# Sheet1.net
KiCad netlist of a schematic drawn in Altium Designer
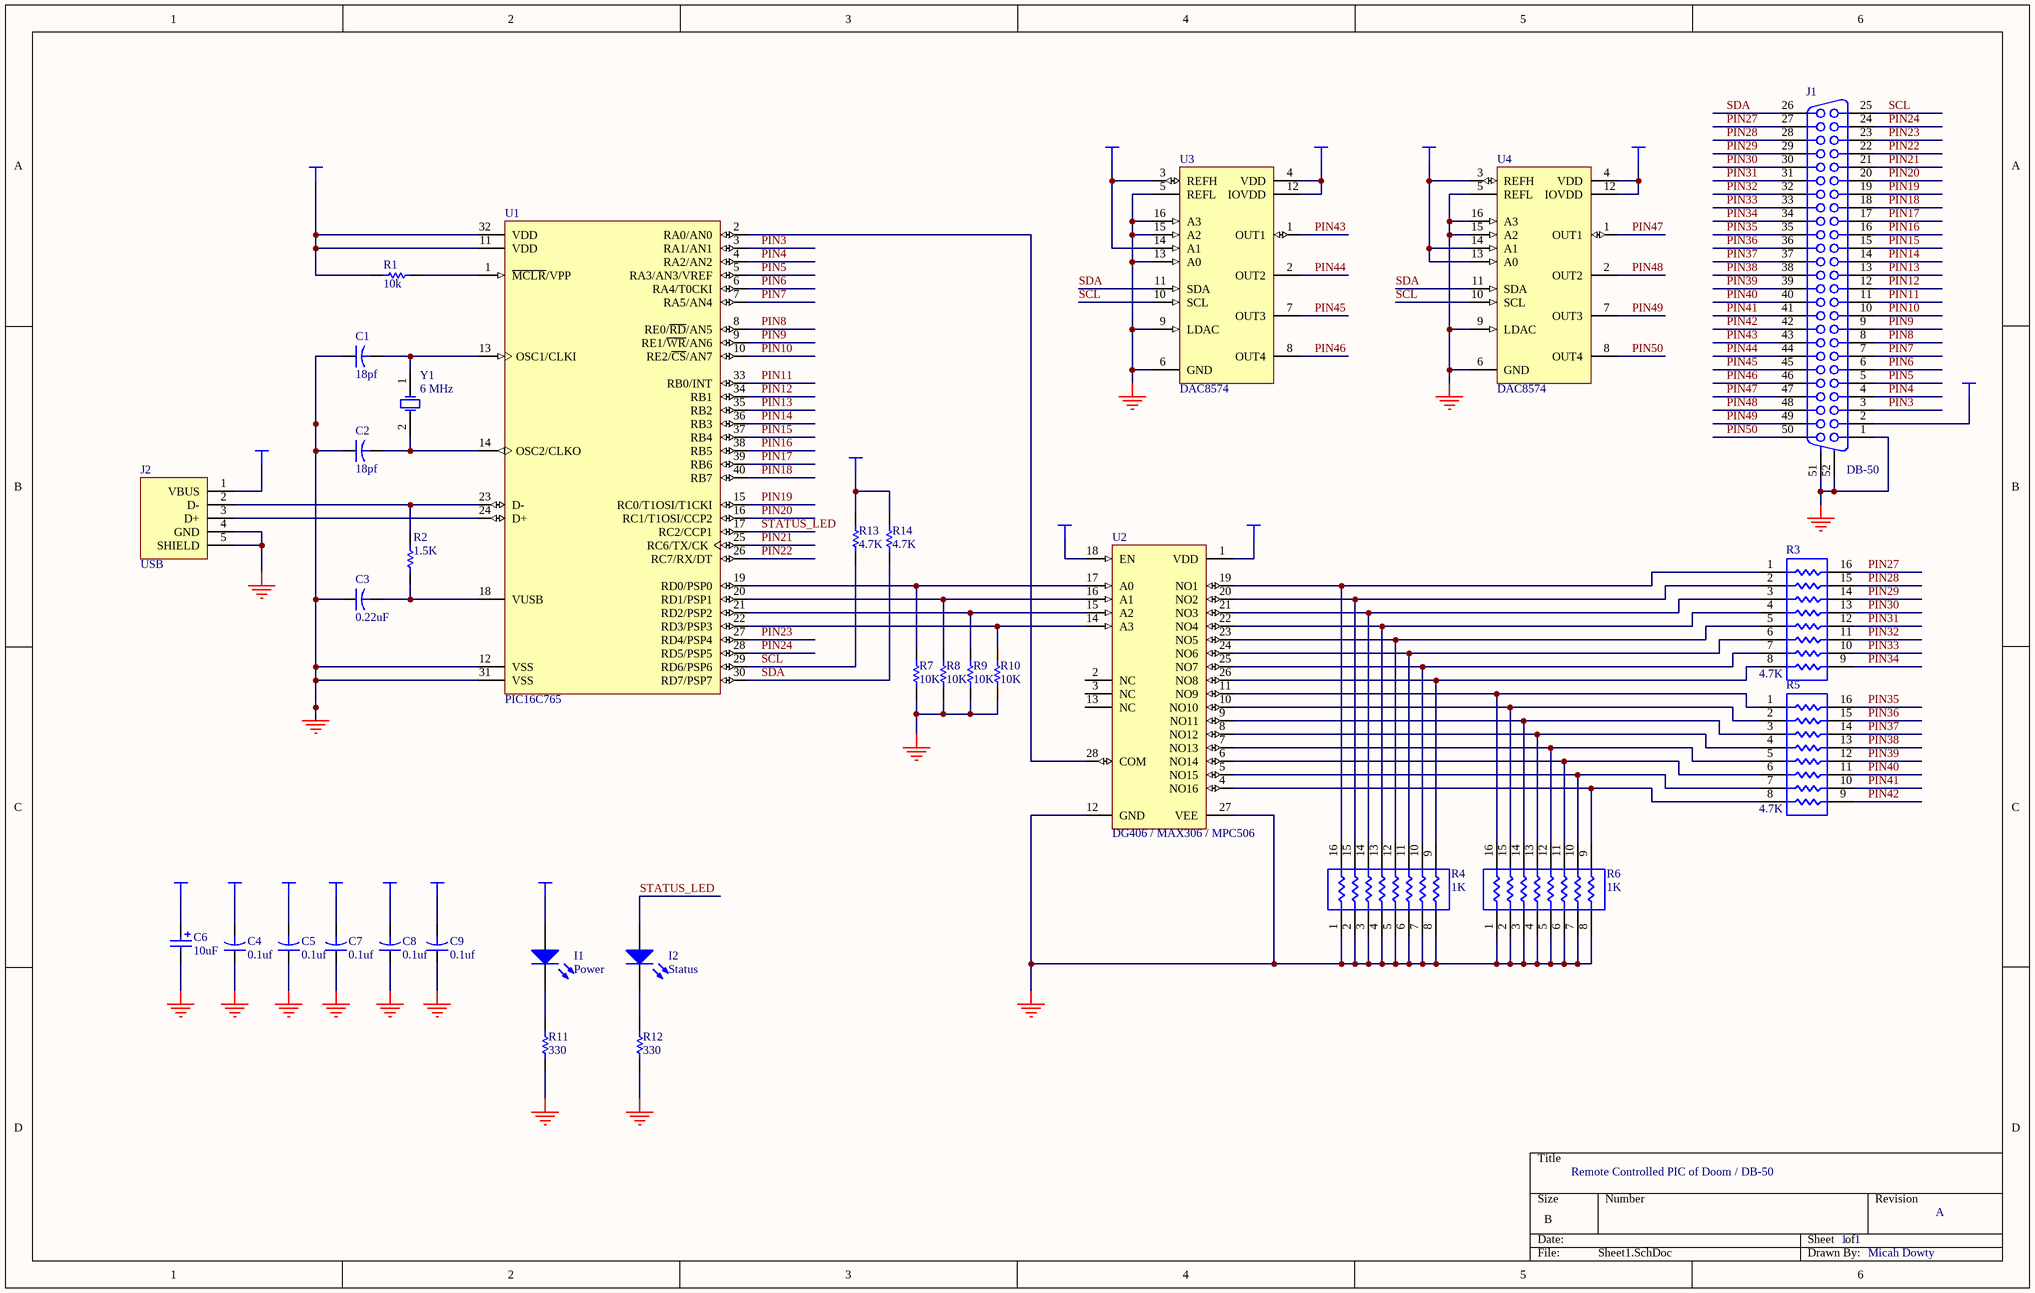
[diagram p0: Sheet1.SchDoc]

(export (version "E")
  (design (tool "Eeschema 10.0.6"))
  (components
    (comp (ref "C1")
      (value "Cap2")
      (footprint "C1005-0402")
      (description "Capacitor")
      (fields
        (field (name "MANUFACTURER") "Generic Components")
        (field (name "ALTIUM_VALUE") "18pf")
        (field (name "PUBLISHER") "Altium Limited")
      )
      (libsource (lib "Miscellaneous Devices") (part "Cap2"))
    )
    (comp (ref "C2")
      (value "Cap2")
      (footprint "C1005-0402")
      (description "Capacitor")
      (fields
        (field (name "MANUFACTURER") "Generic Components")
        (field (name "ALTIUM_VALUE") "18pf")
        (field (name "PUBLISHER") "Altium Limited")
      )
      (libsource (lib "Miscellaneous Devices") (part "Cap2"))
    )
    (comp (ref "C3")
      (value "0.22uF")
      (footprint "C1005-0402")
      (description "Capacitor")
      (fields (field (name "MANUFACTURER") "Generic Components") (field (name "PUBLISHER") "Altium Limited"))
      (libsource (lib "Miscellaneous Devices") (part "Cap2"))
    )
    (comp (ref "C4")
      (value "0.1uf")
      (footprint "C1005-0402")
      (description "Capacitor")
      (fields (field (name "MANUFACTURER") "Generic Components") (field (name "PUBLISHER") "Altium Limited"))
      (libsource (lib "Miscellaneous Devices") (part "Cap2"))
    )
    (comp (ref "C5")
      (value "0.1uf")
      (footprint "C1005-0402")
      (description "Capacitor")
      (fields (field (name "MANUFACTURER") "Generic Components") (field (name "PUBLISHER") "Altium Limited"))
      (libsource (lib "Miscellaneous Devices") (part "Cap2"))
    )
    (comp (ref "C6")
      (value "10uF")
      (footprint "CC4532-1812/Y1.8")
      (description "Polarized Capacitor (Radial)")
      (fields (field (name "MANUFACTURER") "Generic Components") (field (name "PUBLISHER") "Altium Limited"))
      (libsource (lib "Miscellaneous Devices") (part "Cap Pol1"))
    )
    (comp (ref "C7")
      (value "0.1uf")
      (footprint "C1005-0402")
      (description "Capacitor")
      (fields (field (name "MANUFACTURER") "Generic Components") (field (name "PUBLISHER") "Altium Limited"))
      (libsource (lib "Miscellaneous Devices") (part "Cap2"))
    )
    (comp (ref "C8")
      (value "0.1uf")
      (footprint "C1005-0402")
      (description "Capacitor")
      (fields (field (name "MANUFACTURER") "Generic Components") (field (name "PUBLISHER") "Altium Limited"))
      (libsource (lib "Miscellaneous Devices") (part "Cap2"))
    )
    (comp (ref "C9")
      (value "0.1uf")
      (footprint "C1005-0402")
      (description "Capacitor")
      (fields (field (name "MANUFACTURER") "Generic Components") (field (name "PUBLISHER") "Altium Limited"))
      (libsource (lib "Miscellaneous Devices") (part "Cap2"))
    )
    (comp (ref "I1")
      (value "Power")
      (footprint "LED-1-UNBROKE")
      (description "Typical RED GaAs LED")
      (fields (field (name "MANUFACTURER") "Generic Components") (field (name "PUBLISHER") "Altium Limited"))
      (libsource (lib "Miscellaneous Devices") (part "LED1"))
    )
    (comp (ref "I2")
      (value "Status")
      (footprint "LED-1-UNBROKE")
      (description "Typical RED GaAs LED")
      (fields (field (name "MANUFACTURER") "Generic Components") (field (name "PUBLISHER") "Altium Limited"))
      (libsource (lib "Miscellaneous Devices") (part "LED1"))
    )
    (comp (ref "J1")
      (value "DB-50")
      (footprint "NORCOMP-DB50")
      (description "Receptacle Header Assemby")
      (fields (field (name "MANUFACTURER") "Generic Components") (field (name "PUBLISHER") "Altium Limited"))
      (libsource (lib "Miscellaneous Connectors") (part "Connector 50"))
    )
    (comp (ref "J2")
      (value "USB")
      (footprint "USB-TYPEB")
      (description "Header, 4-Pin")
      (fields (field (name "MANUFACTURER") "Generic Components") (field (name "PUBLISHER") "Altium Limited"))
      (libsource (lib "parts") (part "USB Type B"))
    )
    (comp (ref "R1")
      (value "Res1")
      (footprint "C1005-0402")
      (description "Resistor")
      (fields
        (field (name "MANUFACTURER") "Generic Components")
        (field (name "ALTIUM_VALUE") "10k")
        (field (name "PUBLISHER") "Altium Limited")
      )
      (libsource (lib "Miscellaneous Devices") (part "Res1"))
    )
    (comp (ref "R2")
      (value "Res1")
      (footprint "C1005-0402")
      (description "Resistor")
      (fields
        (field (name "MANUFACTURER") "Generic Components")
        (field (name "ALTIUM_VALUE") "1.5K")
        (field (name "PUBLISHER") "Altium Limited")
      )
      (libsource (lib "Miscellaneous Devices") (part "Res1"))
    )
    (comp (ref "R3")
      (value "4.7K")
      (footprint "EXB2HV")
      (description "Resistor Array")
      (fields (field (name "MANUFACTURER") "Generic Components") (field (name "PUBLISHER") "Altium Limited"))
      (libsource (lib "Miscellaneous Devices") (part "Res Pack3"))
    )
    (comp (ref "R4")
      (value "1K")
      (footprint "EXB2HV")
      (description "Resistor Array")
      (fields (field (name "MANUFACTURER") "Generic Components") (field (name "PUBLISHER") "Altium Limited"))
      (libsource (lib "Miscellaneous Devices") (part "Res Pack3"))
    )
    (comp (ref "R5")
      (value "4.7K")
      (footprint "EXB2HV")
      (description "Resistor Array")
      (fields (field (name "MANUFACTURER") "Generic Components") (field (name "PUBLISHER") "Altium Limited"))
      (libsource (lib "Miscellaneous Devices") (part "Res Pack3"))
    )
    (comp (ref "R6")
      (value "1K")
      (footprint "EXB2HV")
      (description "Resistor Array")
      (fields (field (name "MANUFACTURER") "Generic Components") (field (name "PUBLISHER") "Altium Limited"))
      (libsource (lib "Miscellaneous Devices") (part "Res Pack3"))
    )
    (comp (ref "R7")
      (value "10K")
      (footprint "C1005-0402")
      (description "Resistor")
      (fields (field (name "MANUFACTURER") "Generic Components") (field (name "PUBLISHER") "Altium Limited"))
      (libsource (lib "Miscellaneous Devices") (part "Res1"))
    )
    (comp (ref "R8")
      (value "10K")
      (footprint "C1005-0402")
      (description "Resistor")
      (fields (field (name "MANUFACTURER") "Generic Components") (field (name "PUBLISHER") "Altium Limited"))
      (libsource (lib "Miscellaneous Devices") (part "Res1"))
    )
    (comp (ref "R9")
      (value "10K")
      (footprint "C1005-0402")
      (description "Resistor")
      (fields (field (name "MANUFACTURER") "Generic Components") (field (name "PUBLISHER") "Altium Limited"))
      (libsource (lib "Miscellaneous Devices") (part "Res1"))
    )
    (comp (ref "R10")
      (value "10K")
      (footprint "C1005-0402")
      (description "Resistor")
      (fields (field (name "MANUFACTURER") "Generic Components") (field (name "PUBLISHER") "Altium Limited"))
      (libsource (lib "Miscellaneous Devices") (part "Res1"))
    )
    (comp (ref "R11")
      (value "330")
      (footprint "C1005-0402")
      (description "Resistor")
      (fields (field (name "MANUFACTURER") "Generic Components") (field (name "PUBLISHER") "Altium Limited"))
      (libsource (lib "Miscellaneous Devices") (part "Res1"))
    )
    (comp (ref "R12")
      (value "330")
      (footprint "C1005-0402")
      (description "Resistor")
      (fields (field (name "MANUFACTURER") "Generic Components") (field (name "PUBLISHER") "Altium Limited"))
      (libsource (lib "Miscellaneous Devices") (part "Res1"))
    )
    (comp (ref "R13")
      (value "4.7K")
      (footprint "C1005-0402")
      (description "Resistor")
      (fields (field (name "MANUFACTURER") "Generic Components") (field (name "PUBLISHER") "Altium Limited"))
      (libsource (lib "Miscellaneous Devices") (part "Res1"))
    )
    (comp (ref "R14")
      (value "4.7K")
      (footprint "C1005-0402")
      (description "Resistor")
      (fields (field (name "MANUFACTURER") "Generic Components") (field (name "PUBLISHER") "Altium Limited"))
      (libsource (lib "Miscellaneous Devices") (part "Res1"))
    )
    (comp (ref "U1")
      (value "PIC16C765")
      (footprint "DIP-40")
      (description "EPROM-Based 8-Bit CMOS Microcontroller with USB")
      (fields (field (name "MANUFACTURER") "Microchip"))
      (libsource (lib "parts") (part "PIC16C765"))
    )
    (comp (ref "U2")
      (value "DG406 / MAX306 / MPC506")
      (footprint "SO-G28/G7.45")
      (description "Precision, 16-Channel High-performance, CMOS Analog Multiplexer")
      (fields (field (name "MANUFACTURER") "Maxim") (field (name "PUBLISHER") "Altium Limited"))
      (libsource (lib "Maxim Logic Multiplexer") (part "MAX306EPI"))
    )
    (comp (ref "U3")
      (value "DAC8574")
      (footprint "TSSO5X6-G16")
      (description "Quad 16-Bit Low Power Voltage Output I2C Interface DAC")
      (fields (field (name "MANUFACTURER") "Texas Instruments"))
      (libsource (lib "parts") (part "DAC8574"))
    )
    (comp (ref "U4")
      (value "DAC8574")
      (footprint "TSSO5X6-G16")
      (description "Quad 16-Bit Low Power Voltage Output I2C Interface DAC")
      (fields (field (name "MANUFACTURER") "Texas Instruments"))
      (libsource (lib "parts") (part "DAC8574"))
    )
    (comp (ref "Y1")
      (value "6 MHz")
      (footprint "BCY-W2/E4.7")
      (description "Crystal Oscillator")
      (fields (field (name "MANUFACTURER") "Generic Components") (field (name "PUBLISHER") "Altium Limited"))
      (libsource (lib "Miscellaneous Devices") (part "XTAL"))
    )
  )
  (nets
    (net (code "1") (name "/PIN3") (class "Default")
      (node (ref "J1") (pin "3") (pinfunction "3_3") (pintype "passive"))
      (node (ref "U1") (pin "3") (pinfunction "RA1/AN1_3") (pintype "bidirectional"))
    )
    (net (code "2") (name "/PIN4") (class "Default")
      (node (ref "J1") (pin "4") (pinfunction "4_4") (pintype "passive"))
      (node (ref "U1") (pin "4") (pinfunction "RA2/AN2_4") (pintype "bidirectional"))
    )
    (net (code "3") (name "/PIN5") (class "Default")
      (node (ref "J1") (pin "5") (pinfunction "5_5") (pintype "passive"))
      (node (ref "U1") (pin "5") (pinfunction "RA3/AN3/VREF_5") (pintype "bidirectional"))
    )
    (net (code "4") (name "/PIN6") (class "Default")
      (node (ref "J1") (pin "6") (pinfunction "6_6") (pintype "passive"))
      (node (ref "U1") (pin "6") (pinfunction "RA4/T0CKI_6") (pintype "bidirectional"))
    )
    (net (code "5") (name "/PIN7") (class "Default")
      (node (ref "J1") (pin "7") (pinfunction "7_7") (pintype "passive"))
      (node (ref "U1") (pin "7") (pinfunction "RA5/AN4_7") (pintype "bidirectional"))
    )
    (net (code "6") (name "/PIN8") (class "Default")
      (node (ref "J1") (pin "8") (pinfunction "8_8") (pintype "passive"))
      (node (ref "U1") (pin "8") (pinfunction "RE0/~{RD}/AN5_8") (pintype "bidirectional"))
    )
    (net (code "7") (name "/PIN9") (class "Default")
      (node (ref "J1") (pin "9") (pinfunction "9_9") (pintype "passive"))
      (node (ref "U1") (pin "9") (pinfunction "RE1/~{WR}/AN6_9") (pintype "bidirectional"))
    )
    (net (code "8") (name "/PIN10") (class "Default")
      (node (ref "J1") (pin "10") (pinfunction "10_10") (pintype "passive"))
      (node (ref "U1") (pin "10") (pinfunction "RE2/~{CS}/AN7_10") (pintype "bidirectional"))
    )
    (net (code "9") (name "/PIN11") (class "Default")
      (node (ref "J1") (pin "11") (pinfunction "11_11") (pintype "passive"))
      (node (ref "U1") (pin "33") (pinfunction "RB0/INT_33") (pintype "bidirectional"))
    )
    (net (code "10") (name "/PIN12") (class "Default")
      (node (ref "J1") (pin "12") (pinfunction "12_12") (pintype "passive"))
      (node (ref "U1") (pin "34") (pinfunction "RB1_34") (pintype "bidirectional"))
    )
    (net (code "11") (name "/PIN13") (class "Default")
      (node (ref "J1") (pin "13") (pinfunction "13_13") (pintype "passive"))
      (node (ref "U1") (pin "35") (pinfunction "RB2_35") (pintype "bidirectional"))
    )
    (net (code "12") (name "/PIN14") (class "Default")
      (node (ref "J1") (pin "14") (pinfunction "14_14") (pintype "passive"))
      (node (ref "U1") (pin "36") (pinfunction "RB3_36") (pintype "bidirectional"))
    )
    (net (code "13") (name "/PIN15") (class "Default")
      (node (ref "J1") (pin "15") (pinfunction "15_15") (pintype "passive"))
      (node (ref "U1") (pin "37") (pinfunction "RB4_37") (pintype "bidirectional"))
    )
    (net (code "14") (name "/PIN16") (class "Default")
      (node (ref "J1") (pin "16") (pinfunction "16_16") (pintype "passive"))
      (node (ref "U1") (pin "38") (pinfunction "RB5_38") (pintype "bidirectional"))
    )
    (net (code "15") (name "/PIN17") (class "Default")
      (node (ref "J1") (pin "17") (pinfunction "17_17") (pintype "passive"))
      (node (ref "U1") (pin "39") (pinfunction "RB6_39") (pintype "bidirectional"))
    )
    (net (code "16") (name "/PIN18") (class "Default")
      (node (ref "J1") (pin "18") (pinfunction "18_18") (pintype "passive"))
      (node (ref "U1") (pin "40") (pinfunction "RB7_40") (pintype "bidirectional"))
    )
    (net (code "17") (name "/PIN19") (class "Default")
      (node (ref "J1") (pin "19") (pinfunction "19_19") (pintype "passive"))
      (node (ref "U1") (pin "15") (pinfunction "RC0/T1OSI/T1CKI_15") (pintype "bidirectional"))
    )
    (net (code "18") (name "/PIN20") (class "Default")
      (node (ref "J1") (pin "20") (pinfunction "20_20") (pintype "passive"))
      (node (ref "U1") (pin "16") (pinfunction "RC1/T1OSI/CCP2_16") (pintype "bidirectional"))
    )
    (net (code "19") (name "/PIN21") (class "Default")
      (node (ref "J1") (pin "21") (pinfunction "21_21") (pintype "passive"))
      (node (ref "U1") (pin "25") (pinfunction "RC6/TX/CK_25") (pintype "bidirectional"))
    )
    (net (code "20") (name "/PIN22") (class "Default")
      (node (ref "J1") (pin "22") (pinfunction "22_22") (pintype "passive"))
      (node (ref "U1") (pin "26") (pinfunction "RC7/RX/DT_26") (pintype "bidirectional"))
    )
    (net (code "21") (name "/PIN23") (class "Default")
      (node (ref "J1") (pin "23") (pinfunction "23_23") (pintype "passive"))
      (node (ref "U1") (pin "27") (pinfunction "RD4/PSP4_27") (pintype "bidirectional"))
    )
    (net (code "22") (name "/PIN24") (class "Default")
      (node (ref "J1") (pin "24") (pinfunction "24_24") (pintype "passive"))
      (node (ref "U1") (pin "28") (pinfunction "RD5/PSP5_28") (pintype "bidirectional"))
    )
    (net (code "23") (name "/PIN27") (class "Default")
      (node (ref "J1") (pin "27") (pinfunction "27_27") (pintype "passive"))
      (node (ref "R3") (pin "16") (pinfunction "16_16") (pintype "passive"))
    )
    (net (code "24") (name "/PIN28") (class "Default")
      (node (ref "J1") (pin "28") (pinfunction "28_28") (pintype "passive"))
      (node (ref "R3") (pin "15") (pinfunction "15_15") (pintype "passive"))
    )
    (net (code "25") (name "/PIN29") (class "Default")
      (node (ref "J1") (pin "29") (pinfunction "29_29") (pintype "passive"))
      (node (ref "R3") (pin "14") (pinfunction "14_14") (pintype "passive"))
    )
    (net (code "26") (name "/PIN30") (class "Default")
      (node (ref "J1") (pin "30") (pinfunction "30_30") (pintype "passive"))
      (node (ref "R3") (pin "13") (pinfunction "13_13") (pintype "passive"))
    )
    (net (code "27") (name "/PIN31") (class "Default")
      (node (ref "J1") (pin "31") (pinfunction "31_31") (pintype "passive"))
      (node (ref "R3") (pin "12") (pinfunction "12_12") (pintype "passive"))
    )
    (net (code "28") (name "/PIN32") (class "Default")
      (node (ref "J1") (pin "32") (pinfunction "32_32") (pintype "passive"))
      (node (ref "R3") (pin "11") (pinfunction "11_11") (pintype "passive"))
    )
    (net (code "29") (name "/PIN33") (class "Default")
      (node (ref "J1") (pin "33") (pinfunction "33_33") (pintype "passive"))
      (node (ref "R3") (pin "10") (pinfunction "10_10") (pintype "passive"))
    )
    (net (code "30") (name "/PIN34") (class "Default")
      (node (ref "J1") (pin "34") (pinfunction "34_34") (pintype "passive"))
      (node (ref "R3") (pin "9") (pinfunction "9_9") (pintype "passive"))
    )
    (net (code "31") (name "/PIN35") (class "Default")
      (node (ref "J1") (pin "35") (pinfunction "35_35") (pintype "passive"))
      (node (ref "R5") (pin "16") (pinfunction "16_16") (pintype "passive"))
    )
    (net (code "32") (name "/PIN36") (class "Default")
      (node (ref "J1") (pin "36") (pinfunction "36_36") (pintype "passive"))
      (node (ref "R5") (pin "15") (pinfunction "15_15") (pintype "passive"))
    )
    (net (code "33") (name "/PIN37") (class "Default")
      (node (ref "J1") (pin "37") (pinfunction "37_37") (pintype "passive"))
      (node (ref "R5") (pin "14") (pinfunction "14_14") (pintype "passive"))
    )
    (net (code "34") (name "/PIN38") (class "Default")
      (node (ref "J1") (pin "38") (pinfunction "38_38") (pintype "passive"))
      (node (ref "R5") (pin "13") (pinfunction "13_13") (pintype "passive"))
    )
    (net (code "35") (name "/PIN39") (class "Default")
      (node (ref "J1") (pin "39") (pinfunction "39_39") (pintype "passive"))
      (node (ref "R5") (pin "12") (pinfunction "12_12") (pintype "passive"))
    )
    (net (code "36") (name "/PIN40") (class "Default")
      (node (ref "J1") (pin "40") (pinfunction "40_40") (pintype "passive"))
      (node (ref "R5") (pin "11") (pinfunction "11_11") (pintype "passive"))
    )
    (net (code "37") (name "/PIN41") (class "Default")
      (node (ref "J1") (pin "41") (pinfunction "41_41") (pintype "passive"))
      (node (ref "R5") (pin "10") (pinfunction "10_10") (pintype "passive"))
    )
    (net (code "38") (name "/PIN42") (class "Default")
      (node (ref "J1") (pin "42") (pinfunction "42_42") (pintype "passive"))
      (node (ref "R5") (pin "9") (pinfunction "9_9") (pintype "passive"))
    )
    (net (code "39") (name "/PIN43") (class "Default")
      (node (ref "J1") (pin "43") (pinfunction "43_43") (pintype "passive"))
      (node (ref "U3") (pin "1") (pinfunction "OUT1_1") (pintype "bidirectional"))
    )
    (net (code "40") (name "/PIN44") (class "Default")
      (node (ref "J1") (pin "44") (pinfunction "44_44") (pintype "passive"))
      (node (ref "U3") (pin "2") (pinfunction "OUT2_2") (pintype "passive"))
    )
    (net (code "41") (name "/PIN45") (class "Default")
      (node (ref "J1") (pin "45") (pinfunction "45_45") (pintype "passive"))
      (node (ref "U3") (pin "7") (pinfunction "OUT3_7") (pintype "passive"))
    )
    (net (code "42") (name "/PIN46") (class "Default")
      (node (ref "J1") (pin "46") (pinfunction "46_46") (pintype "passive"))
      (node (ref "U3") (pin "8") (pinfunction "OUT4_8") (pintype "passive"))
    )
    (net (code "43") (name "/PIN47") (class "Default")
      (node (ref "J1") (pin "47") (pinfunction "47_47") (pintype "passive"))
      (node (ref "U4") (pin "1") (pinfunction "OUT1_1") (pintype "bidirectional"))
    )
    (net (code "44") (name "/PIN48") (class "Default")
      (node (ref "J1") (pin "48") (pinfunction "48_48") (pintype "passive"))
      (node (ref "U4") (pin "2") (pinfunction "OUT2_2") (pintype "passive"))
    )
    (net (code "45") (name "/PIN49") (class "Default")
      (node (ref "J1") (pin "49") (pinfunction "49_49") (pintype "passive"))
      (node (ref "U4") (pin "7") (pinfunction "OUT3_7") (pintype "passive"))
    )
    (net (code "46") (name "/PIN50") (class "Default")
      (node (ref "J1") (pin "50") (pinfunction "50_50") (pintype "passive"))
      (node (ref "U4") (pin "8") (pinfunction "OUT4_8") (pintype "passive"))
    )
    (net (code "47") (name "/SCL") (class "Default")
      (node (ref "J1") (pin "25") (pinfunction "25_25") (pintype "passive"))
      (node (ref "R13") (pin "1") (pinfunction "1_1") (pintype "passive"))
      (node (ref "U1") (pin "29") (pinfunction "RD6/PSP6_29") (pintype "bidirectional"))
      (node (ref "U3") (pin "10") (pinfunction "SCL_10") (pintype "input"))
      (node (ref "U4") (pin "10") (pinfunction "SCL_10") (pintype "input"))
    )
    (net (code "48") (name "/SDA") (class "Default")
      (node (ref "J1") (pin "26") (pinfunction "26_26") (pintype "passive"))
      (node (ref "R14") (pin "1") (pinfunction "1_1") (pintype "passive"))
      (node (ref "U1") (pin "30") (pinfunction "RD7/PSP7_30") (pintype "bidirectional"))
      (node (ref "U3") (pin "11") (pinfunction "SDA_11") (pintype "input"))
      (node (ref "U4") (pin "11") (pinfunction "SDA_11") (pintype "input"))
    )
    (net (code "49") (name "/STATUS_LED") (class "Default")
      (node (ref "I2") (pin "1") (pinfunction "A_1") (pintype "passive"))
      (node (ref "U1") (pin "17") (pinfunction "RC2/CCP1_17") (pintype "bidirectional"))
    )
    (net (code "50") (name "GND") (class "Default")
      (node (ref "C1") (pin "1") (pinfunction "1_1") (pintype "passive"))
      (node (ref "C2") (pin "1") (pinfunction "1_1") (pintype "passive"))
      (node (ref "C3") (pin "1") (pinfunction "1_1") (pintype "passive"))
      (node (ref "C4") (pin "1") (pinfunction "1_1") (pintype "passive"))
      (node (ref "C5") (pin "1") (pinfunction "1_1") (pintype "passive"))
      (node (ref "C6") (pin "2") (pinfunction "2_2") (pintype "passive"))
      (node (ref "C7") (pin "1") (pinfunction "1_1") (pintype "passive"))
      (node (ref "C8") (pin "1") (pinfunction "1_1") (pintype "passive"))
      (node (ref "C9") (pin "1") (pinfunction "1_1") (pintype "passive"))
      (node (ref "J1") (pin "1") (pinfunction "1_1") (pintype "passive"))
      (node (ref "J1") (pin "51") (pinfunction "MH1_51") (pintype "passive"))
      (node (ref "J1") (pin "52") (pinfunction "MH2_52") (pintype "passive"))
      (node (ref "J2") (pin "4") (pinfunction "GND_4") (pintype "passive"))
      (node (ref "J2") (pin "5") (pinfunction "SHIELD_5") (pintype "power_in"))
      (node (ref "R10") (pin "1") (pinfunction "1_1") (pintype "passive"))
      (node (ref "R11") (pin "2") (pinfunction "2_2") (pintype "passive"))
      (node (ref "R12") (pin "2") (pinfunction "2_2") (pintype "passive"))
      (node (ref "R4") (pin "1") (pinfunction "1_1") (pintype "passive"))
      (node (ref "R4") (pin "2") (pinfunction "2_2") (pintype "passive"))
      (node (ref "R4") (pin "3") (pinfunction "3_3") (pintype "passive"))
      (node (ref "R4") (pin "4") (pinfunction "4_4") (pintype "passive"))
      (node (ref "R4") (pin "5") (pinfunction "5_5") (pintype "passive"))
      (node (ref "R4") (pin "6") (pinfunction "6_6") (pintype "passive"))
      (node (ref "R4") (pin "7") (pinfunction "7_7") (pintype "passive"))
      (node (ref "R4") (pin "8") (pinfunction "8_8") (pintype "passive"))
      (node (ref "R6") (pin "1") (pinfunction "1_1") (pintype "passive"))
      (node (ref "R6") (pin "2") (pinfunction "2_2") (pintype "passive"))
      (node (ref "R6") (pin "3") (pinfunction "3_3") (pintype "passive"))
      (node (ref "R6") (pin "4") (pinfunction "4_4") (pintype "passive"))
      (node (ref "R6") (pin "5") (pinfunction "5_5") (pintype "passive"))
      (node (ref "R6") (pin "6") (pinfunction "6_6") (pintype "passive"))
      (node (ref "R6") (pin "7") (pinfunction "7_7") (pintype "passive"))
      (node (ref "R6") (pin "8") (pinfunction "8_8") (pintype "passive"))
      (node (ref "R7") (pin "1") (pinfunction "1_1") (pintype "passive"))
      (node (ref "R8") (pin "1") (pinfunction "1_1") (pintype "passive"))
      (node (ref "R9") (pin "1") (pinfunction "1_1") (pintype "passive"))
      (node (ref "U1") (pin "12") (pinfunction "VSS_12") (pintype "power_in"))
      (node (ref "U1") (pin "31") (pinfunction "VSS_31") (pintype "power_in"))
      (node (ref "U2") (pin "12") (pinfunction "GND_12") (pintype "power_in"))
      (node (ref "U2") (pin "27") (pinfunction "VEE_27") (pintype "power_in"))
      (node (ref "U3") (pin "13") (pinfunction "A0_13") (pintype "input"))
      (node (ref "U3") (pin "15") (pinfunction "A2_15") (pintype "input"))
      (node (ref "U3") (pin "16") (pinfunction "A3_16") (pintype "input"))
      (node (ref "U3") (pin "5") (pinfunction "REFL_5") (pintype "passive"))
      (node (ref "U3") (pin "6") (pinfunction "GND_6") (pintype "power_in"))
      (node (ref "U3") (pin "9") (pinfunction "LDAC_9") (pintype "input"))
      (node (ref "U4") (pin "15") (pinfunction "A2_15") (pintype "input"))
      (node (ref "U4") (pin "16") (pinfunction "A3_16") (pintype "input"))
      (node (ref "U4") (pin "5") (pinfunction "REFL_5") (pintype "passive"))
      (node (ref "U4") (pin "6") (pinfunction "GND_6") (pintype "power_in"))
      (node (ref "U4") (pin "9") (pinfunction "LDAC_9") (pintype "input"))
    )
    (net (code "51") (name "Net-(I1-K)") (class "Default")
      (node (ref "I1") (pin "2") (pinfunction "K_2") (pintype "passive"))
      (node (ref "R11") (pin "1") (pinfunction "1_1") (pintype "passive"))
    )
    (net (code "52") (name "Net-(I2-K)") (class "Default")
      (node (ref "I2") (pin "2") (pinfunction "K_2") (pintype "passive"))
      (node (ref "R12") (pin "1") (pinfunction "1_1") (pintype "passive"))
    )
    (net (code "53") (name "Net-(J2-D+)") (class "Default")
      (node (ref "J2") (pin "3") (pinfunction "D+_3") (pintype "passive"))
      (node (ref "U1") (pin "24") (pinfunction "D+_24") (pintype "bidirectional"))
    )
    (net (code "54") (name "Net-(J2-D-)") (class "Default")
      (node (ref "J2") (pin "2") (pinfunction "D-_2") (pintype "passive"))
      (node (ref "R2") (pin "2") (pinfunction "2_2") (pintype "passive"))
      (node (ref "U1") (pin "23") (pinfunction "D-_23") (pintype "bidirectional"))
    )
    (net (code "55") (name "Net-(U1-OSC1{slash}CLKI)") (class "Default")
      (node (ref "C1") (pin "2") (pinfunction "2_2") (pintype "passive"))
      (node (ref "U1") (pin "13") (pinfunction "OSC1/CLKI_13") (pintype "input"))
      (node (ref "Y1") (pin "1") (pinfunction "OSC1_1") (pintype "passive"))
    )
    (net (code "56") (name "Net-(U1-OSC2{slash}CLKO)") (class "Default")
      (node (ref "C2") (pin "2") (pinfunction "2_2") (pintype "passive"))
      (node (ref "U1") (pin "14") (pinfunction "OSC2/CLKO_14") (pintype "output"))
      (node (ref "Y1") (pin "2") (pinfunction "OSC2_2") (pintype "passive"))
    )
    (net (code "57") (name "Net-(U1-RA0{slash}AN0)") (class "Default")
      (node (ref "U1") (pin "2") (pinfunction "RA0/AN0_2") (pintype "bidirectional"))
      (node (ref "U2") (pin "28") (pinfunction "COM_28") (pintype "bidirectional"))
    )
    (net (code "58") (name "Net-(U1-RD0{slash}PSP0)") (class "Default")
      (node (ref "R7") (pin "2") (pinfunction "2_2") (pintype "passive"))
      (node (ref "U1") (pin "19") (pinfunction "RD0/PSP0_19") (pintype "bidirectional"))
      (node (ref "U2") (pin "17") (pinfunction "A0_17") (pintype "input"))
    )
    (net (code "59") (name "Net-(U1-RD1{slash}PSP1)") (class "Default")
      (node (ref "R8") (pin "2") (pinfunction "2_2") (pintype "passive"))
      (node (ref "U1") (pin "20") (pinfunction "RD1/PSP1_20") (pintype "bidirectional"))
      (node (ref "U2") (pin "16") (pinfunction "A1_16") (pintype "input"))
    )
    (net (code "60") (name "Net-(U1-RD2{slash}PSP2)") (class "Default")
      (node (ref "R9") (pin "2") (pinfunction "2_2") (pintype "passive"))
      (node (ref "U1") (pin "21") (pinfunction "RD2/PSP2_21") (pintype "bidirectional"))
      (node (ref "U2") (pin "15") (pinfunction "A2_15") (pintype "input"))
    )
    (net (code "61") (name "Net-(U1-RD3{slash}PSP3)") (class "Default")
      (node (ref "R10") (pin "2") (pinfunction "2_2") (pintype "passive"))
      (node (ref "U1") (pin "22") (pinfunction "RD3/PSP3_22") (pintype "bidirectional"))
      (node (ref "U2") (pin "14") (pinfunction "A3_14") (pintype "input"))
    )
    (net (code "62") (name "Net-(U1-VUSB)") (class "Default")
      (node (ref "C3") (pin "2") (pinfunction "2_2") (pintype "passive"))
      (node (ref "R2") (pin "1") (pinfunction "1_1") (pintype "passive"))
      (node (ref "U1") (pin "18") (pinfunction "VUSB_18") (pintype "power_in"))
    )
    (net (code "63") (name "Net-(U1-~{MCLR}{slash}VPP)") (class "Default")
      (node (ref "R1") (pin "1") (pinfunction "1_1") (pintype "passive"))
      (node (ref "U1") (pin "1") (pinfunction "~{MCLR}/VPP_1") (pintype "input"))
    )
    (net (code "64") (name "Net-(U2-NO1)") (class "Default")
      (node (ref "R3") (pin "1") (pinfunction "1_1") (pintype "passive"))
      (node (ref "R4") (pin "16") (pinfunction "16_16") (pintype "passive"))
      (node (ref "U2") (pin "19") (pinfunction "NO1_19") (pintype "bidirectional"))
    )
    (net (code "65") (name "Net-(U2-NO2)") (class "Default")
      (node (ref "R3") (pin "2") (pinfunction "2_2") (pintype "passive"))
      (node (ref "R4") (pin "15") (pinfunction "15_15") (pintype "passive"))
      (node (ref "U2") (pin "20") (pinfunction "NO2_20") (pintype "bidirectional"))
    )
    (net (code "66") (name "Net-(U2-NO3)") (class "Default")
      (node (ref "R3") (pin "3") (pinfunction "3_3") (pintype "passive"))
      (node (ref "R4") (pin "14") (pinfunction "14_14") (pintype "passive"))
      (node (ref "U2") (pin "21") (pinfunction "NO3_21") (pintype "bidirectional"))
    )
    (net (code "67") (name "Net-(U2-NO4)") (class "Default")
      (node (ref "R3") (pin "4") (pinfunction "4_4") (pintype "passive"))
      (node (ref "R4") (pin "13") (pinfunction "13_13") (pintype "passive"))
      (node (ref "U2") (pin "22") (pinfunction "NO4_22") (pintype "bidirectional"))
    )
    (net (code "68") (name "Net-(U2-NO5)") (class "Default")
      (node (ref "R3") (pin "5") (pinfunction "5_5") (pintype "passive"))
      (node (ref "R4") (pin "12") (pinfunction "12_12") (pintype "passive"))
      (node (ref "U2") (pin "23") (pinfunction "NO5_23") (pintype "bidirectional"))
    )
    (net (code "69") (name "Net-(U2-NO6)") (class "Default")
      (node (ref "R3") (pin "6") (pinfunction "6_6") (pintype "passive"))
      (node (ref "R4") (pin "11") (pinfunction "11_11") (pintype "passive"))
      (node (ref "U2") (pin "24") (pinfunction "NO6_24") (pintype "bidirectional"))
    )
    (net (code "70") (name "Net-(U2-NO7)") (class "Default")
      (node (ref "R3") (pin "7") (pinfunction "7_7") (pintype "passive"))
      (node (ref "R4") (pin "10") (pinfunction "10_10") (pintype "passive"))
      (node (ref "U2") (pin "25") (pinfunction "NO7_25") (pintype "bidirectional"))
    )
    (net (code "71") (name "Net-(U2-NO8)") (class "Default")
      (node (ref "R3") (pin "8") (pinfunction "8_8") (pintype "passive"))
      (node (ref "R4") (pin "9") (pinfunction "9_9") (pintype "passive"))
      (node (ref "U2") (pin "26") (pinfunction "NO8_26") (pintype "bidirectional"))
    )
    (net (code "72") (name "Net-(U2-NO9)") (class "Default")
      (node (ref "R5") (pin "1") (pinfunction "1_1") (pintype "passive"))
      (node (ref "R6") (pin "16") (pinfunction "16_16") (pintype "passive"))
      (node (ref "U2") (pin "11") (pinfunction "NO9_11") (pintype "bidirectional"))
    )
    (net (code "73") (name "Net-(U2-NO10)") (class "Default")
      (node (ref "R5") (pin "2") (pinfunction "2_2") (pintype "passive"))
      (node (ref "R6") (pin "15") (pinfunction "15_15") (pintype "passive"))
      (node (ref "U2") (pin "10") (pinfunction "NO10_10") (pintype "bidirectional"))
    )
    (net (code "74") (name "Net-(U2-NO11)") (class "Default")
      (node (ref "R5") (pin "3") (pinfunction "3_3") (pintype "passive"))
      (node (ref "R6") (pin "14") (pinfunction "14_14") (pintype "passive"))
      (node (ref "U2") (pin "9") (pinfunction "NO11_9") (pintype "bidirectional"))
    )
    (net (code "75") (name "Net-(U2-NO12)") (class "Default")
      (node (ref "R5") (pin "4") (pinfunction "4_4") (pintype "passive"))
      (node (ref "R6") (pin "13") (pinfunction "13_13") (pintype "passive"))
      (node (ref "U2") (pin "8") (pinfunction "NO12_8") (pintype "bidirectional"))
    )
    (net (code "76") (name "Net-(U2-NO13)") (class "Default")
      (node (ref "R5") (pin "5") (pinfunction "5_5") (pintype "passive"))
      (node (ref "R6") (pin "12") (pinfunction "12_12") (pintype "passive"))
      (node (ref "U2") (pin "7") (pinfunction "NO13_7") (pintype "bidirectional"))
    )
    (net (code "77") (name "Net-(U2-NO14)") (class "Default")
      (node (ref "R5") (pin "6") (pinfunction "6_6") (pintype "passive"))
      (node (ref "R6") (pin "11") (pinfunction "11_11") (pintype "passive"))
      (node (ref "U2") (pin "6") (pinfunction "NO14_6") (pintype "bidirectional"))
    )
    (net (code "78") (name "Net-(U2-NO15)") (class "Default")
      (node (ref "R5") (pin "7") (pinfunction "7_7") (pintype "passive"))
      (node (ref "R6") (pin "10") (pinfunction "10_10") (pintype "passive"))
      (node (ref "U2") (pin "5") (pinfunction "NO15_5") (pintype "bidirectional"))
    )
    (net (code "79") (name "Net-(U2-NO16)") (class "Default")
      (node (ref "R5") (pin "8") (pinfunction "8_8") (pintype "passive"))
      (node (ref "R6") (pin "9") (pinfunction "9_9") (pintype "passive"))
      (node (ref "U2") (pin "4") (pinfunction "NO16_4") (pintype "bidirectional"))
    )
    (net (code "80") (name "VCC") (class "Default")
      (node (ref "C4") (pin "2") (pinfunction "2_2") (pintype "passive"))
      (node (ref "C5") (pin "2") (pinfunction "2_2") (pintype "passive"))
      (node (ref "C6") (pin "1") (pinfunction "1_1") (pintype "passive"))
      (node (ref "C7") (pin "2") (pinfunction "2_2") (pintype "passive"))
      (node (ref "C8") (pin "2") (pinfunction "2_2") (pintype "passive"))
      (node (ref "C9") (pin "2") (pinfunction "2_2") (pintype "passive"))
      (node (ref "I1") (pin "1") (pinfunction "A_1") (pintype "passive"))
      (node (ref "J1") (pin "2") (pinfunction "2_2") (pintype "passive"))
      (node (ref "J2") (pin "1") (pinfunction "VBUS_1") (pintype "passive"))
      (node (ref "R1") (pin "2") (pinfunction "2_2") (pintype "passive"))
      (node (ref "R13") (pin "2") (pinfunction "2_2") (pintype "passive"))
      (node (ref "R14") (pin "2") (pinfunction "2_2") (pintype "passive"))
      (node (ref "U1") (pin "11") (pinfunction "VDD_11") (pintype "power_in"))
      (node (ref "U1") (pin "32") (pinfunction "VDD_32") (pintype "power_in"))
      (node (ref "U2") (pin "1") (pinfunction "VDD_1") (pintype "power_in"))
      (node (ref "U2") (pin "18") (pinfunction "EN_18") (pintype "input"))
      (node (ref "U3") (pin "12") (pinfunction "IOVDD_12") (pintype "power_in"))
      (node (ref "U3") (pin "14") (pinfunction "A1_14") (pintype "input"))
      (node (ref "U3") (pin "3") (pinfunction "REFH_3") (pintype "bidirectional"))
      (node (ref "U3") (pin "4") (pinfunction "VDD_4") (pintype "power_in"))
      (node (ref "U4") (pin "12") (pinfunction "IOVDD_12") (pintype "power_in"))
      (node (ref "U4") (pin "13") (pinfunction "A0_13") (pintype "input"))
      (node (ref "U4") (pin "14") (pinfunction "A1_14") (pintype "input"))
      (node (ref "U4") (pin "3") (pinfunction "REFH_3") (pintype "bidirectional"))
      (node (ref "U4") (pin "4") (pinfunction "VDD_4") (pintype "power_in"))
    )
    (net (code "81") (name "unconnected-(U2-NC-Pad2)") (class "Default")
      (node (ref "U2") (pin "2") (pinfunction "NC_2") (pintype "passive"))
    )
    (net (code "82") (name "unconnected-(U2-NC-Pad3)") (class "Default")
      (node (ref "U2") (pin "3") (pinfunction "NC_3") (pintype "passive"))
    )
    (net (code "83") (name "unconnected-(U2-NC-Pad13)") (class "Default")
      (node (ref "U2") (pin "13") (pinfunction "NC_13") (pintype "passive"))
    )
  )
)
